# WGPS_Featherwing.net
KiCad netlist of a schematic drawn in EAGLE
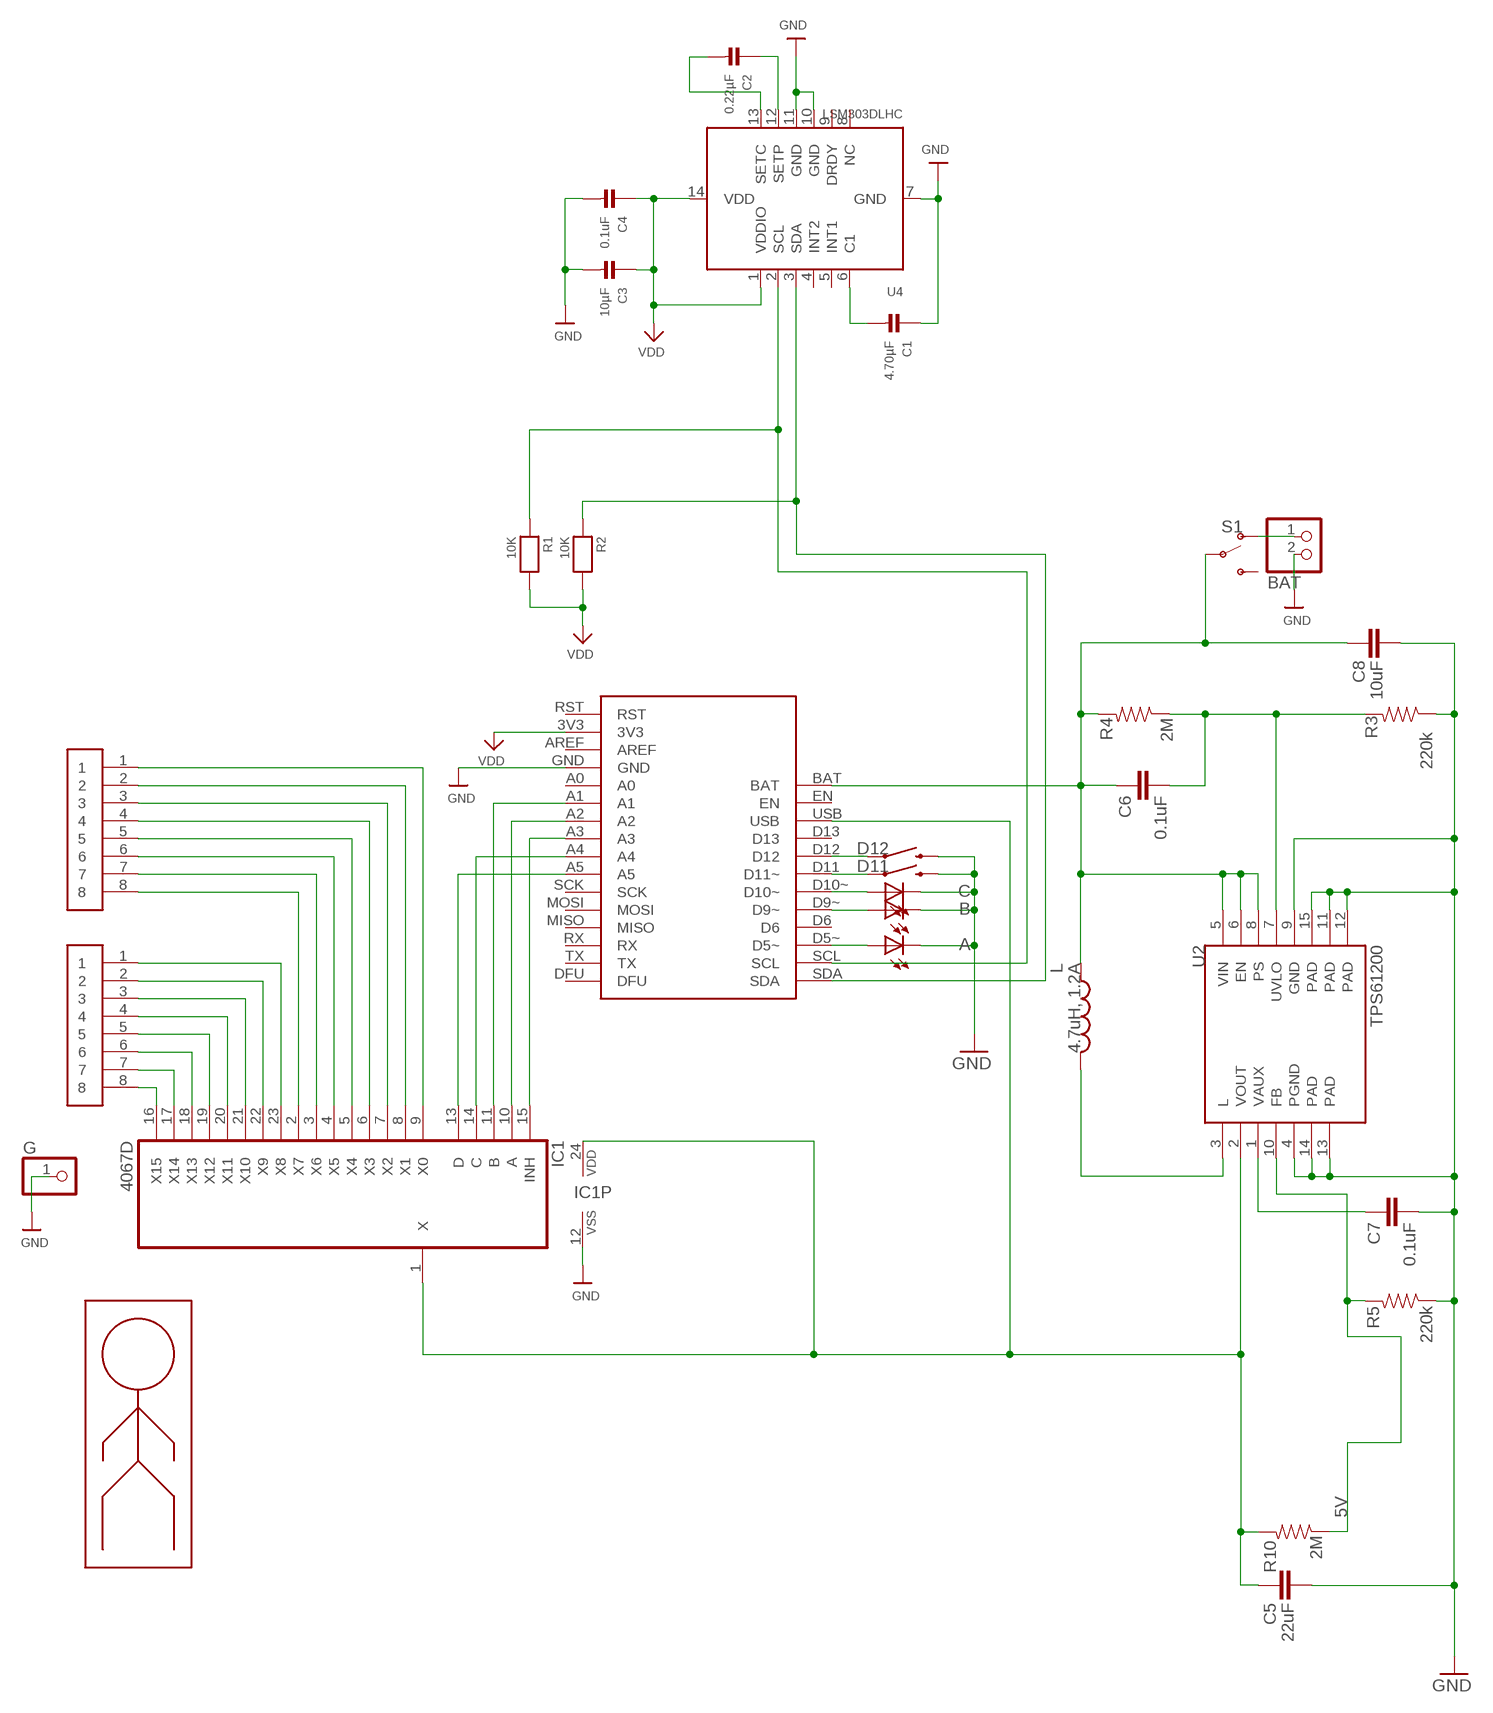
[diagram p0: schematic, sheet 1]

(export (version "E")
  (design (tool "Eeschema 10.0.6"))
  (components
    (comp (ref "A")
      (value "LEDCHIP-LED0805")
      (footprint "eagle-import:CHIP-LED0805")
      (libsource (lib "eagle-import") (part "LEDCHIP-LED0805"))
    )
    (comp (ref "B")
      (value "LEDCHIP-LED0805")
      (footprint "eagle-import:CHIP-LED0805")
      (libsource (lib "eagle-import") (part "LEDCHIP-LED0805"))
    )
    (comp (ref "BAT")
      (value "JST_2PIN-SMT-RA")
      (footprint "eagle-import:JST-PH-2-SMT-RA")
      (libsource (lib "eagle-import") (part "JST_2PIN-SMT-RA"))
    )
    (comp (ref "C")
      (value "LEDCHIP-LED0805")
      (footprint "eagle-import:CHIP-LED0805")
      (libsource (lib "eagle-import") (part "LEDCHIP-LED0805"))
    )
    (comp (ref "C1")
      (value "4.70µF")
      (footprint "eagle-import:_0805")
      (libsource (lib "eagle-import") (part "CAP_CERAMIC_0805"))
    )
    (comp (ref "C2")
      (value "0.22µF")
      (footprint "eagle-import:_0805")
      (libsource (lib "eagle-import") (part "CAP_CERAMIC_0805"))
    )
    (comp (ref "C3")
      (value "10µF")
      (footprint "eagle-import:_0805")
      (libsource (lib "eagle-import") (part "CAP_CERAMIC_0805"))
    )
    (comp (ref "C4")
      (value "0.1uF")
      (footprint "eagle-import:_0805")
      (libsource (lib "eagle-import") (part "CAP_CERAMIC_0805"))
    )
    (comp (ref "C5")
      (value "22uF")
      (footprint "eagle-import:0805")
      (libsource (lib "eagle-import") (part "CAP0805"))
    )
    (comp (ref "C6")
      (value "0.1uF")
      (footprint "eagle-import:0603-CAP")
      (libsource (lib "eagle-import") (part "CAP0603-CAP"))
    )
    (comp (ref "C7")
      (value "0.1uF")
      (footprint "eagle-import:0603-CAP")
      (libsource (lib "eagle-import") (part "CAP0603-CAP"))
    )
    (comp (ref "C8")
      (value "10uF")
      (footprint "eagle-import:1206")
      (libsource (lib "eagle-import") (part "CAP1206"))
    )
    (comp (ref "D11")
      (value "MOMENTARY-SWITCH-SPST-SMD-6.0X3.5MM")
      (footprint "eagle-import:TACTILE_SWITCH_SMD_6.0X3.5MM")
      (libsource (lib "eagle-import") (part "MOMENTARY-SWITCH-SPST-SMD-6.0X3.5MM"))
    )
    (comp (ref "D12")
      (value "MOMENTARY-SWITCH-SPST-SMD-6.0X3.5MM")
      (footprint "eagle-import:TACTILE_SWITCH_SMD_6.0X3.5MM")
      (libsource (lib "eagle-import") (part "MOMENTARY-SWITCH-SPST-SMD-6.0X3.5MM"))
    )
    (comp (ref "G")
      (value "PINHD-1X1CB")
      (footprint "eagle-import:1X01-CLEANBIG")
      (libsource (lib "eagle-import") (part "PINHD-1X1CB"))
    )
    (comp (ref "IC1")
      (value "4067D")
      (footprint "eagle-import:SO24W")
      (libsource (lib "eagle-import") (part "4067D"))
    )
    (comp (ref "L")
      (value "4.7uH, 1.2A")
      (footprint "eagle-import:CDRH2D09")
      (libsource (lib "eagle-import") (part "INDUCTOR."))
    )
    (comp (ref "R1")
      (value "10K")
      (footprint "eagle-import:_0805")
      (libsource (lib "eagle-import") (part "RESISTOR_0805"))
    )
    (comp (ref "R2")
      (value "10K")
      (footprint "eagle-import:_0805")
      (libsource (lib "eagle-import") (part "RESISTOR_0805"))
    )
    (comp (ref "R3")
      (value "220k")
      (footprint "eagle-import:0603-RES")
      (libsource (lib "eagle-import") (part "RESISTOR0603-RES"))
    )
    (comp (ref "R4")
      (value "2M")
      (footprint "eagle-import:0603-RES")
      (libsource (lib "eagle-import") (part "RESISTOR0603-RES"))
    )
    (comp (ref "R5")
      (value "220k")
      (footprint "eagle-import:0603-RES")
      (libsource (lib "eagle-import") (part "RESISTOR0603-RES"))
    )
    (comp (ref "R10")
      (value "2M")
      (footprint "eagle-import:0603-RES")
      (libsource (lib "eagle-import") (part "RESISTOR0603-RES"))
    )
    (comp (ref "S1")
      (value "SWITCH-SPDT-SMD-RIGHT-ANGLE")
      (footprint "eagle-import:SWITCH_SPST_SMD_A")
      (libsource (lib "eagle-import") (part "SWITCH-SPDT-SMD-RIGHT-ANGLE"))
    )
    (comp (ref "U$1")
      (value "SMD_FEATHERWING_BLE_32U4")
      (footprint "eagle-import:FEATHERWING_MALE_SMD_HEADERS_0.1")
      (libsource (lib "eagle-import") (part "SMD_FEATHERWING_BLE_32U4"))
    )
    (comp (ref "U$6")
      (value "SMD_JST_1X8")
      (footprint "eagle-import:SMD_JST_1X8")
      (libsource (lib "eagle-import") (part "SMD_JST_1X8"))
    )
    (comp (ref "U$7")
      (value "SMD_JST_1X8")
      (footprint "eagle-import:SMD_JST_1X8")
      (libsource (lib "eagle-import") (part "SMD_JST_1X8"))
    )
    (comp (ref "U$16")
      (value "MAN_LOGO")
      (footprint "eagle-import:MAN_LOGO_0.6")
      (libsource (lib "eagle-import") (part "MAN_LOGO"))
    )
    (comp (ref "U2")
      (value "TPS61200")
      (footprint "eagle-import:QFN-10_PAD")
      (libsource (lib "eagle-import") (part "TPS61200"))
    )
    (comp (ref "U4")
      (value "LSM303DLHC")
      (footprint "eagle-import:LGA14")
      (libsource (lib "eagle-import") (part "LSM303DLHC"))
    )
  )
  (nets
    (net (code "1") (name "/5V") (class "Default")
      (node (ref "R10") (pin "1") (pinfunction "1_1") (pintype "passive"))
      (node (ref "R5") (pin "2") (pinfunction "2_2") (pintype "passive"))
      (node (ref "U2") (pin "10") (pinfunction "FB_10") (pintype "passive"))
    )
    (net (code "2") (name "GND") (class "Default")
      (node (ref "A") (pin "C") (pinfunction "C_C") (pintype "passive"))
      (node (ref "B") (pin "C") (pinfunction "C_C") (pintype "passive"))
      (node (ref "BAT") (pin "2") (pinfunction "1_2") (pintype "passive"))
      (node (ref "C") (pin "C") (pinfunction "C_C") (pintype "passive"))
      (node (ref "C1") (pin "1") (pinfunction "P$1_1") (pintype "passive"))
      (node (ref "C3") (pin "2") (pinfunction "P$2_2") (pintype "passive"))
      (node (ref "C4") (pin "2") (pinfunction "P$2_2") (pintype "passive"))
      (node (ref "C5") (pin "2") (pinfunction "2_2") (pintype "passive"))
      (node (ref "C7") (pin "2") (pinfunction "2_2") (pintype "passive"))
      (node (ref "C8") (pin "2") (pinfunction "2_2") (pintype "passive"))
      (node (ref "D11") (pin "2") (pinfunction "2_2") (pintype "passive"))
      (node (ref "D12") (pin "2") (pinfunction "2_2") (pintype "passive"))
      (node (ref "G") (pin "1") (pinfunction "1_1") (pintype "passive"))
      (node (ref "IC1") (pin "12") (pinfunction "VSS_12") (pintype "power_in"))
      (node (ref "R3") (pin "1") (pinfunction "1_1") (pintype "passive"))
      (node (ref "R5") (pin "1") (pinfunction "1_1") (pintype "passive"))
      (node (ref "U$1") (pin "GND") (pinfunction "GND_GND") (pintype "bidirectional"))
      (node (ref "U2") (pin "11") (pinfunction "PAD_11") (pintype "power_in"))
      (node (ref "U2") (pin "12") (pinfunction "PAD_12") (pintype "power_in"))
      (node (ref "U2") (pin "13") (pinfunction "PAD_13") (pintype "power_in"))
      (node (ref "U2") (pin "14") (pinfunction "PAD_14") (pintype "power_in"))
      (node (ref "U2") (pin "15") (pinfunction "PAD_15") (pintype "power_in"))
      (node (ref "U2") (pin "4") (pinfunction "PGND_4") (pintype "power_in"))
      (node (ref "U2") (pin "9") (pinfunction "GND_9") (pintype "power_in"))
      (node (ref "U4") (pin "10") (pinfunction "GND_10") (pintype "power_in"))
      (node (ref "U4") (pin "11") (pinfunction "GND_11") (pintype "power_in"))
      (node (ref "U4") (pin "7") (pinfunction "GND_7") (pintype "power_in"))
    )
    (net (code "3") (name "Net-(BAT-2)") (class "Default")
      (node (ref "BAT") (pin "1") (pinfunction "2_1") (pintype "passive"))
      (node (ref "S1") (pin "1") (pinfunction "O_1") (pintype "passive"))
    )
    (net (code "4") (name "Net-(C1-P$2)") (class "Default")
      (node (ref "C1") (pin "2") (pinfunction "P$2_2") (pintype "passive"))
      (node (ref "U4") (pin "6") (pinfunction "C1_6") (pintype "bidirectional"))
    )
    (net (code "5") (name "Net-(C2-P$1)") (class "Default")
      (node (ref "C2") (pin "1") (pinfunction "P$1_1") (pintype "passive"))
      (node (ref "U4") (pin "12") (pinfunction "SETP_12") (pintype "bidirectional"))
    )
    (net (code "6") (name "Net-(C2-P$2)") (class "Default")
      (node (ref "C2") (pin "2") (pinfunction "P$2_2") (pintype "passive"))
      (node (ref "U4") (pin "13") (pinfunction "SETC_13") (pintype "bidirectional"))
    )
    (net (code "7") (name "Net-(D12-Pad1)") (class "Default")
      (node (ref "D12") (pin "1") (pinfunction "1_1") (pintype "passive"))
      (node (ref "U$1") (pin "D12") (pinfunction "D12_D12") (pintype "bidirectional"))
    )
    (net (code "8") (name "Net-(IC1A-A)") (class "Default")
      (node (ref "IC1") (pin "10") (pinfunction "A_10") (pintype "input"))
      (node (ref "U$1") (pin "A2") (pinfunction "A2_A2") (pintype "bidirectional"))
    )
    (net (code "9") (name "Net-(IC1A-B)") (class "Default")
      (node (ref "IC1") (pin "11") (pinfunction "B_11") (pintype "input"))
      (node (ref "U$1") (pin "A1") (pinfunction "A1_A1") (pintype "bidirectional"))
    )
    (net (code "10") (name "Net-(IC1A-C)") (class "Default")
      (node (ref "IC1") (pin "14") (pinfunction "C_14") (pintype "input"))
      (node (ref "U$1") (pin "A4") (pinfunction "A4_A4") (pintype "bidirectional"))
    )
    (net (code "11") (name "Net-(IC1A-D)") (class "Default")
      (node (ref "IC1") (pin "13") (pinfunction "D_13") (pintype "input"))
      (node (ref "U$1") (pin "A5") (pinfunction "A5_A5") (pintype "bidirectional"))
    )
    (net (code "12") (name "Net-(IC1A-INH)") (class "Default")
      (node (ref "IC1") (pin "15") (pinfunction "INH_15") (pintype "input"))
      (node (ref "U$1") (pin "A3") (pinfunction "A3_A3") (pintype "bidirectional"))
    )
    (net (code "13") (name "Net-(IC1A-X)") (class "Default")
      (node (ref "C5") (pin "1") (pinfunction "1_1") (pintype "passive"))
      (node (ref "IC1") (pin "1") (pinfunction "X_1") (pintype "output"))
      (node (ref "IC1") (pin "24") (pinfunction "VDD_24") (pintype "power_in"))
      (node (ref "R10") (pin "2") (pinfunction "2_2") (pintype "passive"))
      (node (ref "U$1") (pin "USB") (pinfunction "USB_USB") (pintype "bidirectional"))
      (node (ref "U2") (pin "2") (pinfunction "VOUT_2") (pintype "passive"))
    )
    (net (code "14") (name "Net-(IC1A-X0)") (class "Default")
      (node (ref "IC1") (pin "9") (pinfunction "X0_9") (pintype "input"))
      (node (ref "U$6") (pin "1") (pinfunction "1_1") (pintype "bidirectional"))
    )
    (net (code "15") (name "Net-(IC1A-X1)") (class "Default")
      (node (ref "IC1") (pin "8") (pinfunction "X1_8") (pintype "input"))
      (node (ref "U$6") (pin "2") (pinfunction "2_2") (pintype "bidirectional"))
    )
    (net (code "16") (name "Net-(IC1A-X2)") (class "Default")
      (node (ref "IC1") (pin "7") (pinfunction "X2_7") (pintype "input"))
      (node (ref "U$6") (pin "3") (pinfunction "3_3") (pintype "bidirectional"))
    )
    (net (code "17") (name "Net-(IC1A-X3)") (class "Default")
      (node (ref "IC1") (pin "6") (pinfunction "X3_6") (pintype "input"))
      (node (ref "U$6") (pin "4") (pinfunction "4_4") (pintype "bidirectional"))
    )
    (net (code "18") (name "Net-(IC1A-X4)") (class "Default")
      (node (ref "IC1") (pin "5") (pinfunction "X4_5") (pintype "input"))
      (node (ref "U$6") (pin "5") (pinfunction "5_5") (pintype "bidirectional"))
    )
    (net (code "19") (name "Net-(IC1A-X5)") (class "Default")
      (node (ref "IC1") (pin "4") (pinfunction "X5_4") (pintype "input"))
      (node (ref "U$6") (pin "6") (pinfunction "6_6") (pintype "bidirectional"))
    )
    (net (code "20") (name "Net-(IC1A-X6)") (class "Default")
      (node (ref "IC1") (pin "3") (pinfunction "X6_3") (pintype "input"))
      (node (ref "U$6") (pin "7") (pinfunction "7_7") (pintype "bidirectional"))
    )
    (net (code "21") (name "Net-(IC1A-X7)") (class "Default")
      (node (ref "IC1") (pin "2") (pinfunction "X7_2") (pintype "input"))
      (node (ref "U$6") (pin "8") (pinfunction "8_8") (pintype "bidirectional"))
    )
    (net (code "22") (name "Net-(IC1A-X8)") (class "Default")
      (node (ref "IC1") (pin "23") (pinfunction "X8_23") (pintype "input"))
      (node (ref "U$7") (pin "1") (pinfunction "1_1") (pintype "bidirectional"))
    )
    (net (code "23") (name "Net-(IC1A-X9)") (class "Default")
      (node (ref "IC1") (pin "22") (pinfunction "X9_22") (pintype "input"))
      (node (ref "U$7") (pin "2") (pinfunction "2_2") (pintype "bidirectional"))
    )
    (net (code "24") (name "Net-(IC1A-X10)") (class "Default")
      (node (ref "IC1") (pin "21") (pinfunction "X10_21") (pintype "input"))
      (node (ref "U$7") (pin "3") (pinfunction "3_3") (pintype "bidirectional"))
    )
    (net (code "25") (name "Net-(IC1A-X11)") (class "Default")
      (node (ref "IC1") (pin "20") (pinfunction "X11_20") (pintype "input"))
      (node (ref "U$7") (pin "4") (pinfunction "4_4") (pintype "bidirectional"))
    )
    (net (code "26") (name "Net-(IC1A-X12)") (class "Default")
      (node (ref "IC1") (pin "19") (pinfunction "X12_19") (pintype "input"))
      (node (ref "U$7") (pin "5") (pinfunction "5_5") (pintype "bidirectional"))
    )
    (net (code "27") (name "Net-(IC1A-X13)") (class "Default")
      (node (ref "IC1") (pin "18") (pinfunction "X13_18") (pintype "input"))
      (node (ref "U$7") (pin "6") (pinfunction "6_6") (pintype "bidirectional"))
    )
    (net (code "28") (name "Net-(IC1A-X14)") (class "Default")
      (node (ref "IC1") (pin "17") (pinfunction "X14_17") (pintype "input"))
      (node (ref "U$7") (pin "7") (pinfunction "7_7") (pintype "bidirectional"))
    )
    (net (code "29") (name "Net-(IC1A-X15)") (class "Default")
      (node (ref "IC1") (pin "16") (pinfunction "X15_16") (pintype "input"))
      (node (ref "U$7") (pin "8") (pinfunction "8_8") (pintype "bidirectional"))
    )
    (net (code "30") (name "Net-(L-1)") (class "Default")
      (node (ref "L") (pin "P$1") (pinfunction "1_P$1") (pintype "passive"))
      (node (ref "U2") (pin "3") (pinfunction "L_3") (pintype "passive"))
    )
    (net (code "31") (name "Net-(L-2)") (class "Default")
      (node (ref "C6") (pin "1") (pinfunction "1_1") (pintype "passive"))
      (node (ref "C8") (pin "1") (pinfunction "1_1") (pintype "passive"))
      (node (ref "L") (pin "P$2") (pinfunction "2_P$2") (pintype "passive"))
      (node (ref "R4") (pin "2") (pinfunction "2_2") (pintype "passive"))
      (node (ref "S1") (pin "2") (pinfunction "P_2") (pintype "passive"))
      (node (ref "U$1") (pin "BAT") (pinfunction "BAT_BAT") (pintype "bidirectional"))
      (node (ref "U2") (pin "5") (pinfunction "VIN_5") (pintype "power_in"))
      (node (ref "U2") (pin "6") (pinfunction "EN_6") (pintype "input"))
      (node (ref "U2") (pin "8") (pinfunction "PS_8") (pintype "input"))
    )
    (net (code "32") (name "Net-(U$1-D5~{})") (class "Default")
      (node (ref "A") (pin "A") (pinfunction "A_A") (pintype "passive"))
      (node (ref "U$1") (pin "D5~") (pinfunction "D5~{}_D5~") (pintype "bidirectional"))
    )
    (net (code "33") (name "Net-(U$1-D9~{})") (class "Default")
      (node (ref "B") (pin "A") (pinfunction "A_A") (pintype "passive"))
      (node (ref "U$1") (pin "D9~") (pinfunction "D9~{}_D9~") (pintype "bidirectional"))
    )
    (net (code "34") (name "Net-(U$1-D10~{})") (class "Default")
      (node (ref "C") (pin "A") (pinfunction "A_A") (pintype "passive"))
      (node (ref "U$1") (pin "D10~") (pinfunction "D10~{}_D10~") (pintype "bidirectional"))
    )
    (net (code "35") (name "Net-(U$1-D11~{})") (class "Default")
      (node (ref "D11") (pin "1") (pinfunction "1_1") (pintype "passive"))
      (node (ref "U$1") (pin "D11") (pinfunction "D11~{}_D11") (pintype "bidirectional"))
    )
    (net (code "36") (name "Net-(U2-UVLO)") (class "Default")
      (node (ref "C6") (pin "2") (pinfunction "2_2") (pintype "passive"))
      (node (ref "R3") (pin "2") (pinfunction "2_2") (pintype "passive"))
      (node (ref "R4") (pin "1") (pinfunction "1_1") (pintype "passive"))
      (node (ref "U2") (pin "7") (pinfunction "UVLO_7") (pintype "passive"))
    )
    (net (code "37") (name "Net-(U2-VAUX)") (class "Default")
      (node (ref "C7") (pin "1") (pinfunction "1_1") (pintype "passive"))
      (node (ref "U2") (pin "1") (pinfunction "VAUX_1") (pintype "passive"))
    )
    (net (code "38") (name "Net-(U4-SCL)") (class "Default")
      (node (ref "R1") (pin "1") (pinfunction "1_1") (pintype "passive"))
      (node (ref "U$1") (pin "SCL") (pinfunction "SCL_SCL") (pintype "bidirectional"))
      (node (ref "U4") (pin "2") (pinfunction "SCL_2") (pintype "bidirectional"))
    )
    (net (code "39") (name "Net-(U4-SDA)") (class "Default")
      (node (ref "R2") (pin "1") (pinfunction "1_1") (pintype "passive"))
      (node (ref "U$1") (pin "SDA") (pinfunction "SDA_SDA") (pintype "bidirectional"))
      (node (ref "U4") (pin "3") (pinfunction "SDA_3") (pintype "bidirectional"))
    )
    (net (code "40") (name "VDD") (class "Default")
      (node (ref "C3") (pin "1") (pinfunction "P$1_1") (pintype "passive"))
      (node (ref "C4") (pin "1") (pinfunction "P$1_1") (pintype "passive"))
      (node (ref "R1") (pin "2") (pinfunction "2_2") (pintype "passive"))
      (node (ref "R2") (pin "2") (pinfunction "2_2") (pintype "passive"))
      (node (ref "U$1") (pin "3V3") (pinfunction "3V3_3V3") (pintype "bidirectional"))
      (node (ref "U4") (pin "1") (pinfunction "VDDIO_1") (pintype "power_in"))
      (node (ref "U4") (pin "14") (pinfunction "VDD_14") (pintype "power_in"))
    )
    (net (code "41") (name "unconnected-(S1-S-Pad3)") (class "Default")
      (node (ref "S1") (pin "3") (pinfunction "S_3") (pintype "passive"))
    )
    (net (code "42") (name "unconnected-(U$1-PadA0)") (class "Default")
      (node (ref "U$1") (pin "A0") (pinfunction "A0_A0") (pintype "bidirectional"))
    )
    (net (code "43") (name "unconnected-(U$1-PadAREF)") (class "Default")
      (node (ref "U$1") (pin "AREF") (pinfunction "AREF_AREF") (pintype "bidirectional"))
    )
    (net (code "44") (name "unconnected-(U$1-PadD6)") (class "Default")
      (node (ref "U$1") (pin "D6") (pinfunction "D6_D6") (pintype "bidirectional"))
    )
    (net (code "45") (name "unconnected-(U$1-PadD13)") (class "Default")
      (node (ref "U$1") (pin "D13") (pinfunction "D13_D13") (pintype "bidirectional"))
    )
    (net (code "46") (name "unconnected-(U$1-PadDFU)") (class "Default")
      (node (ref "U$1") (pin "DFU") (pinfunction "DFU_DFU") (pintype "bidirectional"))
    )
    (net (code "47") (name "unconnected-(U$1-PadEN)") (class "Default")
      (node (ref "U$1") (pin "EN") (pinfunction "EN_EN") (pintype "bidirectional"))
    )
    (net (code "48") (name "unconnected-(U$1-PadMISO)") (class "Default")
      (node (ref "U$1") (pin "MISO") (pinfunction "MISO_MISO") (pintype "bidirectional"))
    )
    (net (code "49") (name "unconnected-(U$1-PadMOSI)") (class "Default")
      (node (ref "U$1") (pin "MOSI") (pinfunction "MOSI_MOSI") (pintype "bidirectional"))
    )
    (net (code "50") (name "unconnected-(U$1-PadRST)") (class "Default")
      (node (ref "U$1") (pin "RST") (pinfunction "RST_RST") (pintype "bidirectional"))
    )
    (net (code "51") (name "unconnected-(U$1-PadRX)") (class "Default")
      (node (ref "U$1") (pin "RX") (pinfunction "RX_RX") (pintype "bidirectional"))
    )
    (net (code "52") (name "unconnected-(U$1-PadSCK)") (class "Default")
      (node (ref "U$1") (pin "SCK") (pinfunction "SCK_SCK") (pintype "bidirectional"))
    )
    (net (code "53") (name "unconnected-(U$1-PadTX)") (class "Default")
      (node (ref "U$1") (pin "TX") (pinfunction "TX_TX") (pintype "bidirectional"))
    )
    (net (code "54") (name "unconnected-(U4-DRDY-Pad9)") (class "Default")
      (node (ref "U4") (pin "9") (pinfunction "DRDY_9") (pintype "output"))
    )
    (net (code "55") (name "unconnected-(U4-INT1-Pad5)") (class "Default")
      (node (ref "U4") (pin "5") (pinfunction "INT1_5") (pintype "output"))
    )
    (net (code "56") (name "unconnected-(U4-INT2-Pad4)") (class "Default")
      (node (ref "U4") (pin "4") (pinfunction "INT2_4") (pintype "output"))
    )
    (net (code "57") (name "unconnected-(U4-NC-Pad8)") (class "Default")
      (node (ref "U4") (pin "8") (pinfunction "NC_8") (pintype "bidirectional"))
    )
  )
)
